# SH3_-_BATTERY_MANAGER.net
KiCad netlist of a schematic drawn in Altium Designer
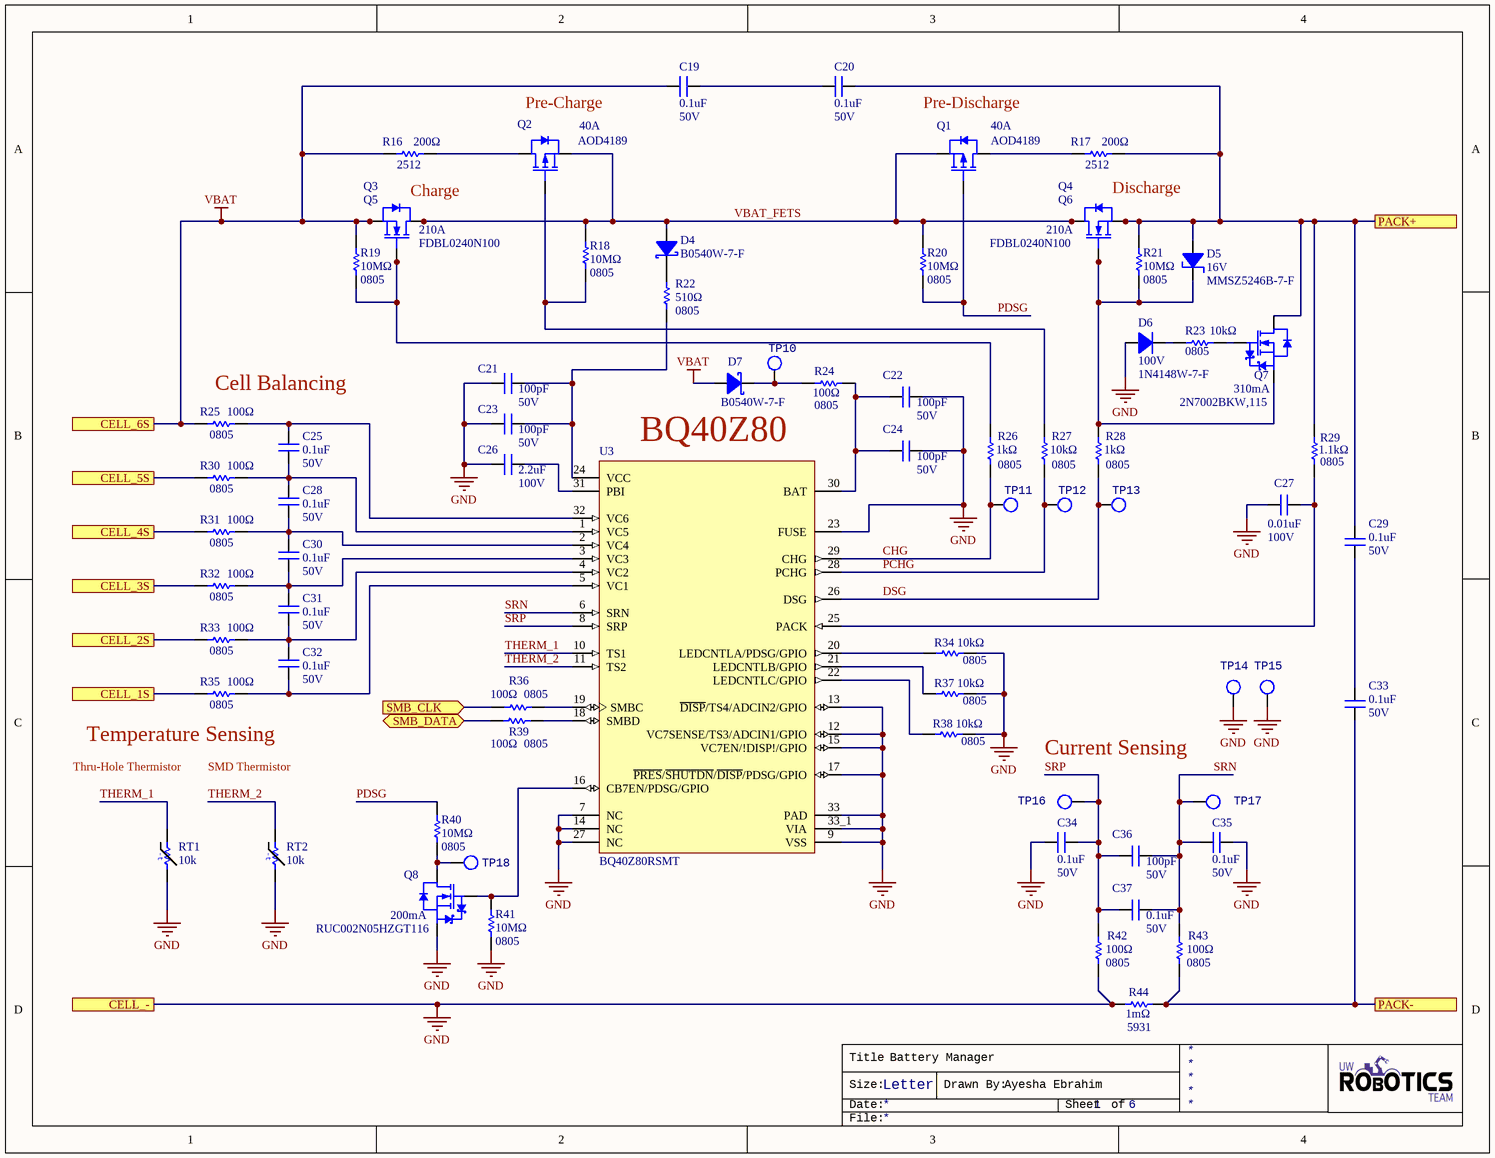
[diagram p0: SH3 - BATTERY MANAGER.SchDoc]

(export (version "E")
  (design (tool "Eeschema 10.0.6"))
  (components
    (comp (ref "C19")
      (value "0.1uF")
      (footprint "CAPC2012X140N")
      (description "CAP CER 0.1UF 50V X7R 0805")
      (fields
        (field (name "TOLERANCE") "10%")
        (field (name "VOLTAGE RATING") "50V")
        (field (name "Comment") "CAP_0.1uF_50V_0805")
      )
      (libsource (lib "UWRT_Schematic_Library_2020") (part "CAP_0.1uF_50V_0805"))
    )
    (comp (ref "C20")
      (value "0.1uF")
      (footprint "CAPC2012X140N")
      (description "CAP CER 0.1UF 50V X7R 0805")
      (fields
        (field (name "TOLERANCE") "10%")
        (field (name "VOLTAGE RATING") "50V")
        (field (name "Comment") "CAP_0.1uF_50V_0805")
      )
      (libsource (lib "UWRT_Schematic_Library_2020") (part "CAP_0.1uF_50V_0805"))
    )
    (comp (ref "C21")
      (value "100pF")
      (footprint "CAPC2012X140N")
      (description "CAP CER 100PF 50V C0G/NP0 0805")
      (fields
        (field (name "TOLERANCE") "5%")
        (field (name "VOLTAGE RATING") "50V")
        (field (name "Comment") "CAP_100pF_50V_0805")
      )
      (libsource (lib "UWRT_Schematic_Library_2020") (part "CAP_100pF_50V_0805"))
    )
    (comp (ref "C22")
      (value "100pF")
      (footprint "CAPC2012X140N")
      (description "CAP CER 100PF 50V C0G/NP0 0805")
      (fields
        (field (name "TOLERANCE") "5%")
        (field (name "VOLTAGE RATING") "50V")
        (field (name "Comment") "CAP_100pF_50V_0805")
      )
      (libsource (lib "UWRT_Schematic_Library_2020") (part "CAP_100pF_50V_0805"))
    )
    (comp (ref "C23")
      (value "100pF")
      (footprint "CAPC2012X140N")
      (description "CAP CER 100PF 50V C0G/NP0 0805")
      (fields
        (field (name "TOLERANCE") "5%")
        (field (name "VOLTAGE RATING") "50V")
        (field (name "Comment") "CAP_100pF_50V_0805")
      )
      (libsource (lib "UWRT_Schematic_Library_2020") (part "CAP_100pF_50V_0805"))
    )
    (comp (ref "C24")
      (value "100pF")
      (footprint "CAPC2012X140N")
      (description "CAP CER 100PF 50V C0G/NP0 0805")
      (fields
        (field (name "TOLERANCE") "5%")
        (field (name "VOLTAGE RATING") "50V")
        (field (name "Comment") "CAP_100pF_50V_0805")
      )
      (libsource (lib "UWRT_Schematic_Library_2020") (part "CAP_100pF_50V_0805"))
    )
    (comp (ref "C25")
      (value "0.1uF")
      (footprint "CAPC2012X140N")
      (description "CAP CER 0.1UF 50V X7R 0805")
      (fields
        (field (name "TOLERANCE") "10%")
        (field (name "VOLTAGE RATING") "50V")
        (field (name "Comment") "CAP_0.1uF_50V_0805")
      )
      (libsource (lib "UWRT_Schematic_Library_2020") (part "CAP_0.1uF_50V_0805"))
    )
    (comp (ref "C26")
      (value "2.2uF")
      (footprint "CAPC1210(3225)")
      (description "CAP CER 2.2UF 100V X7R 1210")
      (fields
        (field (name "TOLERANCE") "10%")
        (field (name "VOLTAGE RATING") "100V")
        (field (name "Comment") "CAP_2.2uF_100V_1210")
      )
      (libsource (lib "UWRT_Schematic_Library_2020") (part "CAP_2.2uF_100V_1210"))
    )
    (comp (ref "C27")
      (value "0.01uF")
      (footprint "CAPC2012X140N")
      (description "CAP CER 10000PF 100V X7R 0805")
      (fields
        (field (name "TOLERANCE") "10%")
        (field (name "VOLTAGE RATING") "100V")
        (field (name "Comment") "CAP_0.01uF_100V_0805")
      )
      (libsource (lib "UWRT_Schematic_Library_2020") (part "CAP_0.01uF_100V_0805"))
    )
    (comp (ref "C28")
      (value "0.1uF")
      (footprint "CAPC2012X140N")
      (description "CAP CER 0.1UF 50V X7R 0805")
      (fields
        (field (name "TOLERANCE") "10%")
        (field (name "VOLTAGE RATING") "50V")
        (field (name "Comment") "CAP_0.1uF_50V_0805")
      )
      (libsource (lib "UWRT_Schematic_Library_2020") (part "CAP_0.1uF_50V_0805"))
    )
    (comp (ref "C29")
      (value "0.1uF")
      (footprint "CAPC2012X140N")
      (description "CAP CER 0.1UF 50V X7R 0805")
      (fields
        (field (name "TOLERANCE") "10%")
        (field (name "VOLTAGE RATING") "50V")
        (field (name "Comment") "CAP_0.1uF_50V_0805")
      )
      (libsource (lib "UWRT_Schematic_Library_2020") (part "CAP_0.1uF_50V_0805"))
    )
    (comp (ref "C30")
      (value "0.1uF")
      (footprint "CAPC2012X140N")
      (description "CAP CER 0.1UF 50V X7R 0805")
      (fields
        (field (name "TOLERANCE") "10%")
        (field (name "VOLTAGE RATING") "50V")
        (field (name "Comment") "CAP_0.1uF_50V_0805")
      )
      (libsource (lib "UWRT_Schematic_Library_2020") (part "CAP_0.1uF_50V_0805"))
    )
    (comp (ref "C31")
      (value "0.1uF")
      (footprint "CAPC2012X140N")
      (description "CAP CER 0.1UF 50V X7R 0805")
      (fields
        (field (name "TOLERANCE") "10%")
        (field (name "VOLTAGE RATING") "50V")
        (field (name "Comment") "CAP_0.1uF_50V_0805")
      )
      (libsource (lib "UWRT_Schematic_Library_2020") (part "CAP_0.1uF_50V_0805"))
    )
    (comp (ref "C32")
      (value "0.1uF")
      (footprint "CAPC2012X140N")
      (description "CAP CER 0.1UF 50V X7R 0805")
      (fields
        (field (name "TOLERANCE") "10%")
        (field (name "VOLTAGE RATING") "50V")
        (field (name "Comment") "CAP_0.1uF_50V_0805")
      )
      (libsource (lib "UWRT_Schematic_Library_2020") (part "CAP_0.1uF_50V_0805"))
    )
    (comp (ref "C33")
      (value "0.1uF")
      (footprint "CAPC2012X140N")
      (description "CAP CER 0.1UF 50V X7R 0805")
      (fields
        (field (name "TOLERANCE") "10%")
        (field (name "VOLTAGE RATING") "50V")
        (field (name "Comment") "CAP_0.1uF_50V_0805")
      )
      (libsource (lib "UWRT_Schematic_Library_2020") (part "CAP_0.1uF_50V_0805"))
    )
    (comp (ref "C34")
      (value "0.1uF")
      (footprint "CAPC2012X140N")
      (description "CAP CER 0.1UF 50V X7R 0805")
      (fields
        (field (name "TOLERANCE") "10%")
        (field (name "VOLTAGE RATING") "50V")
        (field (name "Comment") "CAP_0.1uF_50V_0805")
      )
      (libsource (lib "UWRT_Schematic_Library_2020") (part "CAP_0.1uF_50V_0805"))
    )
    (comp (ref "C35")
      (value "0.1uF")
      (footprint "CAPC2012X140N")
      (description "CAP CER 0.1UF 50V X7R 0805")
      (fields
        (field (name "TOLERANCE") "10%")
        (field (name "VOLTAGE RATING") "50V")
        (field (name "Comment") "CAP_0.1uF_50V_0805")
      )
      (libsource (lib "UWRT_Schematic_Library_2020") (part "CAP_0.1uF_50V_0805"))
    )
    (comp (ref "C36")
      (value "100pF")
      (footprint "CAPC2012X140N")
      (description "CAP CER 100PF 50V C0G/NP0 0805")
      (fields
        (field (name "TOLERANCE") "5%")
        (field (name "VOLTAGE RATING") "50V")
        (field (name "Comment") "CAP_100pF_50V_0805")
      )
      (libsource (lib "UWRT_Schematic_Library_2020") (part "CAP_100pF_50V_0805"))
    )
    (comp (ref "C37")
      (value "0.1uF")
      (footprint "CAPC2012X140N")
      (description "CAP CER 0.1UF 50V X7R 0805")
      (fields
        (field (name "TOLERANCE") "10%")
        (field (name "VOLTAGE RATING") "50V")
        (field (name "Comment") "CAP_0.1uF_50V_0805")
      )
      (libsource (lib "UWRT_Schematic_Library_2020") (part "CAP_0.1uF_50V_0805"))
    )
    (comp (ref "D4")
      (value "B0540W-7-F")
      (footprint "SOD-123_FLAT")
      (description "DIODE SCHOTTKY 40V 500MA SOD123")
      (fields
        (field (name "MANUFACTURER") "Diodes Inc.")
        (field (name "OCTOPART") "https://octopart.com/b0540w-7-f-diodes+inc.-325656")
        (field (name "MANUFACTURER PART NUMBER 1") "B0540W-7-F")
      )
      (libsource (lib "UWRT_Schematic_Library_2020") (part "DIO_SCHOTTKY_40V_500mA"))
    )
    (comp (ref "D5")
      (value "DIO_ZENER_16V")
      (footprint "SOD-123_FLAT")
      (description "DIODE ZENER 16V 500MW SOD123")
      (fields
        (field (name "MANUFACTURER PART NUMBER 1") "MMSZ5246B-7-F")
        (field (name "ZENER VOLTAGE") "16V")
        (field (name "TOLERANCE") "5%")
      )
      (libsource (lib "UWRT_Schematic_Library_2020") (part "DIO_ZENER_16V"))
    )
    (comp (ref "D6")
      (value "100V")
      (footprint "SOD-123_FLAT")
      (description "DIODE GEN PURP 100V 300MA SOD123")
      (fields
        (field (name "MANUFACTURER PART NUMBER 1") "1N4148W-7-F")
        (field (name "Comment") "1N4148W-7-F")
      )
      (libsource (lib "UWRT_Schematic_Library_2020") (part "DIO_100V_300mA"))
    )
    (comp (ref "D7")
      (value "B0540W-7-F")
      (footprint "SOD-123_FLAT")
      (description "DIODE SCHOTTKY 40V 500MA SOD123")
      (fields
        (field (name "MANUFACTURER") "Diodes Inc.")
        (field (name "MANUFACTURER PART NUMBER") "B0540W-7-F")
        (field (name "OCTOPART") "https://octopart.com/b0540w-7-f-diodes+inc.-325656")
      )
      (libsource (lib "UWRT_Schematic_Library_2020") (part "DIO_SCHOTTKY_40V_500mA"))
    )
    (comp (ref "Q1")
      (value "PMOS_40V_40A")
      (footprint "D-PAK")
      (description "MOSFET P-CH 40V 40A TO252")
      (fields (field (name "MANUFACTURER PART NUMBER 1") "AOD4189") (field (name "ID") "40A"))
      (libsource (lib "UWRT_Schematic_Library_2020") (part "PMOS_40V_40A"))
    )
    (comp (ref "Q2")
      (value "PMOS_40V_40A")
      (footprint "D-PAK")
      (description "MOSFET P-CH 40V 40A TO252")
      (fields (field (name "MANUFACTURER PART NUMBER 1") "AOD4189") (field (name "ID") "40A"))
      (libsource (lib "UWRT_Schematic_Library_2020") (part "PMOS_40V_40A"))
    )
    (comp (ref "Q3")
      (value "NMOS_100V_210A")
      (footprint "8-HPSOF")
      (description "MOSFET N-CH 100V 210A POWER56")
      (fields (field (name "MANUFACTURER PART NUMBER 1") "FDBL0240N100") (field (name "ID") "210A"))
      (libsource (lib "UWRT_Schematic_Library_2020") (part "NMOS_100V_210A"))
    )
    (comp (ref "Q4")
      (value "NMOS_100V_210A")
      (footprint "8-HPSOF")
      (description "MOSFET N-CH 100V 210A POWER56")
      (fields (field (name "MANUFACTURER PART NUMBER 1") "FDBL0240N100") (field (name "ID") "210A"))
      (libsource (lib "UWRT_Schematic_Library_2020") (part "NMOS_100V_210A"))
    )
    (comp (ref "Q5")
      (value "NMOS_100V_210A")
      (footprint "8-HPSOF")
      (description "MOSFET N-CH 100V 210A POWER56")
      (libsource (lib "UWRT_Schematic_Library_2020") (part "NMOS_100V_210A"))
    )
    (comp (ref "Q6")
      (value "NMOS_100V_210A")
      (footprint "8-HPSOF")
      (description "MOSFET N-CH 100V 210A POWER56")
      (libsource (lib "UWRT_Schematic_Library_2020") (part "NMOS_100V_210A"))
    )
    (comp (ref "Q7")
      (value "NMOS_60V_310mA")
      (footprint "SOT323")
      (description "NMOS N-CH 60V 310mA SOT-323")
      (fields (field (name "MANUFACTURER PART NUMBER 1") "2N7002BKW,115") (field (name "ID") "310mA"))
      (libsource (lib "UWRT_Schematic_Library_2020") (part "NMOS_60V_310mA"))
    )
    (comp (ref "Q8")
      (value "NMOS_50V_200mA")
      (footprint "SOT23-3")
      (description "NMOS N-CH 50V 200mA 1.2V DRIVE SOT-23-3")
      (fields (field (name "MANUFACTURER PART NUMBER 1") "RUC002N05HZGT116") (field (name "ID") "200mA"))
      (libsource (lib "UWRT_Schematic_Library_2020") (part "NMOS_50V_200mA"))
    )
    (comp (ref "R16")
      (value "200Ω")
      (footprint "RESC6532X75N")
      (description "RES 200 OHM 5% 1W 2512")
      (fields
        (field (name "PACKAGE") "2512")
        (field (name "TOLERANCE") "5%")
        (field (name "Comment") "RES_200Ω_2512")
      )
      (libsource (lib "UWRT_Schematic_Library_2020") (part "RES_200Ω_2512"))
    )
    (comp (ref "R17")
      (value "200Ω")
      (footprint "RESC6532X75N")
      (description "RES 200 OHM 5% 1W 2512")
      (fields
        (field (name "PACKAGE") "2512")
        (field (name "TOLERANCE") "5%")
        (field (name "Comment") "RES_200Ω_2512")
      )
      (libsource (lib "UWRT_Schematic_Library_2020") (part "RES_200Ω_2512"))
    )
    (comp (ref "R18")
      (value "10MΩ")
      (footprint "RESC2012X60N")
      (description "RES SMD 10M OHM 5% 1/8W 0805")
      (fields
        (field (name "TOLERANCE") "5%")
        (field (name "CASE CODE (IMPERIAL)") "0805")
        (field (name "Comment") "RES_10MΩ_0805")
      )
      (libsource (lib "UWRT_Schematic_Library_2020") (part "RES_10MΩ_0805"))
    )
    (comp (ref "R19")
      (value "10MΩ")
      (footprint "RESC2012X60N")
      (description "RES SMD 10M OHM 5% 1/8W 0805")
      (fields
        (field (name "TOLERANCE") "5%")
        (field (name "CASE CODE (IMPERIAL)") "0805")
        (field (name "Comment") "RES_10MΩ_0805")
      )
      (libsource (lib "UWRT_Schematic_Library_2020") (part "RES_10MΩ_0805"))
    )
    (comp (ref "R20")
      (value "10MΩ")
      (footprint "RESC2012X60N")
      (description "RES SMD 10M OHM 5% 1/8W 0805")
      (fields
        (field (name "TOLERANCE") "5%")
        (field (name "CASE CODE (IMPERIAL)") "0805")
        (field (name "Comment") "RES_10MΩ_0805")
      )
      (libsource (lib "UWRT_Schematic_Library_2020") (part "RES_10MΩ_0805"))
    )
    (comp (ref "R21")
      (value "10MΩ")
      (footprint "RESC2012X60N")
      (description "RES SMD 10M OHM 5% 1/8W 0805")
      (fields
        (field (name "TOLERANCE") "5%")
        (field (name "CASE CODE (IMPERIAL)") "0805")
        (field (name "Comment") "RES_10MΩ_0805")
      )
      (libsource (lib "UWRT_Schematic_Library_2020") (part "RES_10MΩ_0805"))
    )
    (comp (ref "R22")
      (value "510Ω")
      (footprint "RESC2012X60N")
      (description "RES SMD 510 OHM 1% 1/8W 0805")
      (fields
        (field (name "CASE CODE (IMPERIAL)") "0805")
        (field (name "TOLERANCE") "1%")
        (field (name "Comment") "RES_510Ω_0805")
      )
      (libsource (lib "UWRT_Schematic_Library_2020") (part "RES_510Ω_0805"))
    )
    (comp (ref "R23")
      (value "10kΩ")
      (footprint "RESC2012X60N")
      (description "RES SMD 10K OHM 1% 1/8W 0805")
      (fields
        (field (name "CASE CODE (IMPERIAL)") "0805")
        (field (name "TOLERANCE") "1%")
        (field (name "Comment") "RES_10kΩ_0805")
      )
      (libsource (lib "UWRT_Schematic_Library_2020") (part "RES_10kΩ_0805"))
    )
    (comp (ref "R24")
      (value "100Ω")
      (footprint "RESC2012X60N")
      (description "RES SMD 100 OHM 1% 1/8W 0805")
      (fields (field (name "CASE CODE (IMPERIAL)") "0805") (field (name "Comment") "RES_100Ω_0805"))
      (libsource (lib "UWRT_Schematic_Library_2020") (part "RES_100Ω_0805"))
    )
    (comp (ref "R25")
      (value "100Ω")
      (footprint "RESC2012X60N")
      (description "RES SMD 100 OHM 1% 1/8W 0805")
      (fields (field (name "CASE CODE (IMPERIAL)") "0805") (field (name "Comment") "RES_100Ω_0805"))
      (libsource (lib "UWRT_Schematic_Library_2020") (part "RES_100Ω_0805"))
    )
    (comp (ref "R26")
      (value "1kΩ")
      (footprint "RESC2012X60N")
      (description "RES SMD 1K OHM 1% 1/8W 0805")
      (fields
        (field (name "CASE CODE (IMPERIAL)") "0805")
        (field (name "TOLERANCE") "1%")
        (field (name "Comment") "RES_1kΩ_0805")
      )
      (libsource (lib "UWRT_Schematic_Library_2020") (part "RES_1kΩ_0805"))
    )
    (comp (ref "R27")
      (value "10kΩ")
      (footprint "RESC2012X60N")
      (description "RES SMD 10K OHM 1% 1/8W 0805")
      (fields
        (field (name "CASE CODE (IMPERIAL)") "0805")
        (field (name "TOLERANCE") "1%")
        (field (name "Comment") "RES_10kΩ_0805")
      )
      (libsource (lib "UWRT_Schematic_Library_2020") (part "RES_10kΩ_0805"))
    )
    (comp (ref "R28")
      (value "1kΩ")
      (footprint "RESC2012X60N")
      (description "RES SMD 1K OHM 1% 1/8W 0805")
      (fields
        (field (name "CASE CODE (IMPERIAL)") "0805")
        (field (name "TOLERANCE") "1%")
        (field (name "Comment") "RES_1kΩ_0805")
      )
      (libsource (lib "UWRT_Schematic_Library_2020") (part "RES_1kΩ_0805"))
    )
    (comp (ref "R29")
      (value "1.1kΩ")
      (footprint "RESC2012X60N")
      (description "RES SMD 1.1K OHM 1% 1/8W 0805")
      (fields
        (field (name "CASE CODE (IMPERIAL)") "0805")
        (field (name "TOLERANCE") "1%")
        (field (name "Comment") "RES_1.1kΩ_0805")
      )
      (libsource (lib "UWRT_Schematic_Library_2020") (part "RES_1.1kΩ_0805"))
    )
    (comp (ref "R30")
      (value "100Ω")
      (footprint "RESC2012X60N")
      (description "RES SMD 100 OHM 1% 1/8W 0805")
      (fields (field (name "CASE CODE (IMPERIAL)") "0805") (field (name "Comment") "RES_100Ω_0805"))
      (libsource (lib "UWRT_Schematic_Library_2020") (part "RES_100Ω_0805"))
    )
    (comp (ref "R31")
      (value "100Ω")
      (footprint "RESC2012X60N")
      (description "RES SMD 100 OHM 1% 1/8W 0805")
      (fields (field (name "CASE CODE (IMPERIAL)") "0805") (field (name "Comment") "RES_100Ω_0805"))
      (libsource (lib "UWRT_Schematic_Library_2020") (part "RES_100Ω_0805"))
    )
    (comp (ref "R32")
      (value "100Ω")
      (footprint "RESC2012X60N")
      (description "RES SMD 100 OHM 1% 1/8W 0805")
      (fields (field (name "CASE CODE (IMPERIAL)") "0805") (field (name "Comment") "RES_100Ω_0805"))
      (libsource (lib "UWRT_Schematic_Library_2020") (part "RES_100Ω_0805"))
    )
    (comp (ref "R33")
      (value "100Ω")
      (footprint "RESC2012X60N")
      (description "RES SMD 100 OHM 1% 1/8W 0805")
      (fields (field (name "CASE CODE (IMPERIAL)") "0805") (field (name "Comment") "RES_100Ω_0805"))
      (libsource (lib "UWRT_Schematic_Library_2020") (part "RES_100Ω_0805"))
    )
    (comp (ref "R34")
      (value "10kΩ")
      (footprint "RESC2012X60N")
      (description "RES SMD 10K OHM 1% 1/8W 0805")
      (fields
        (field (name "CASE CODE (IMPERIAL)") "0805")
        (field (name "TOLERANCE") "1%")
        (field (name "Comment") "RES_10kΩ_0805")
      )
      (libsource (lib "UWRT_Schematic_Library_2020") (part "RES_10kΩ_0805"))
    )
    (comp (ref "R35")
      (value "100Ω")
      (footprint "RESC2012X60N")
      (description "RES SMD 100 OHM 1% 1/8W 0805")
      (fields (field (name "CASE CODE (IMPERIAL)") "0805") (field (name "Comment") "RES_100Ω_0805"))
      (libsource (lib "UWRT_Schematic_Library_2020") (part "RES_100Ω_0805"))
    )
    (comp (ref "R36")
      (value "100Ω")
      (footprint "RESC2012X60N")
      (description "RES SMD 100 OHM 1% 1/8W 0805")
      (fields (field (name "CASE CODE (IMPERIAL)") "0805") (field (name "Comment") "RES_100Ω_0805"))
      (libsource (lib "UWRT_Schematic_Library_2020") (part "RES_100Ω_0805"))
    )
    (comp (ref "R37")
      (value "10kΩ")
      (footprint "RESC2012X60N")
      (description "RES SMD 10K OHM 1% 1/8W 0805")
      (fields
        (field (name "CASE CODE (IMPERIAL)") "0805")
        (field (name "TOLERANCE") "1%")
        (field (name "Comment") "RES_10kΩ_0805")
      )
      (libsource (lib "UWRT_Schematic_Library_2020") (part "RES_10kΩ_0805"))
    )
    (comp (ref "R38")
      (value "10kΩ")
      (footprint "RESC2012X60N")
      (description "RES SMD 10K OHM 1% 1/8W 0805")
      (fields
        (field (name "CASE CODE (IMPERIAL)") "0805")
        (field (name "TOLERANCE") "1%")
        (field (name "Comment") "RES_10kΩ_0805")
      )
      (libsource (lib "UWRT_Schematic_Library_2020") (part "RES_10kΩ_0805"))
    )
    (comp (ref "R39")
      (value "100Ω")
      (footprint "RESC2012X60N")
      (description "RES SMD 100 OHM 1% 1/8W 0805")
      (fields (field (name "CASE CODE (IMPERIAL)") "0805") (field (name "Comment") "RES_100Ω_0805"))
      (libsource (lib "UWRT_Schematic_Library_2020") (part "RES_100Ω_0805"))
    )
    (comp (ref "R40")
      (value "10MΩ")
      (footprint "RESC2012X60N")
      (description "RES SMD 10M OHM 5% 1/8W 0805")
      (fields
        (field (name "TOLERANCE") "5%")
        (field (name "CASE CODE (IMPERIAL)") "0805")
        (field (name "Comment") "RES_10MΩ_0805")
      )
      (libsource (lib "UWRT_Schematic_Library_2020") (part "RES_10MΩ_0805"))
    )
    (comp (ref "R41")
      (value "10MΩ")
      (footprint "RESC2012X60N")
      (description "RES SMD 10M OHM 5% 1/8W 0805")
      (fields
        (field (name "TOLERANCE") "5%")
        (field (name "CASE CODE (IMPERIAL)") "0805")
        (field (name "Comment") "RES_10MΩ_0805")
      )
      (libsource (lib "UWRT_Schematic_Library_2020") (part "RES_10MΩ_0805"))
    )
    (comp (ref "R42")
      (value "100Ω")
      (footprint "RESC2012X60N")
      (description "RES SMD 100 OHM 1% 1/8W 0805")
      (fields (field (name "CASE CODE (IMPERIAL)") "0805") (field (name "Comment") "RES_100Ω_0805"))
      (libsource (lib "UWRT_Schematic_Library_2020") (part "RES_100Ω_0805"))
    )
    (comp (ref "R43")
      (value "100Ω")
      (footprint "RESC2012X60N")
      (description "RES SMD 100 OHM 1% 1/8W 0805")
      (fields (field (name "CASE CODE (IMPERIAL)") "0805") (field (name "Comment") "RES_100Ω_0805"))
      (libsource (lib "UWRT_Schematic_Library_2020") (part "RES_100Ω_0805"))
    )
    (comp (ref "R44")
      (value "1mΩ")
      (footprint "RES-5931")
      (description "RES 0.001 OHM 1% 10W 5931")
      (fields
        (field (name "PACKAGE") "5931")
        (field (name "TOLERANCE") "1%")
        (field (name "Comment") "RES_1mΩ_5931")
      )
      (libsource (lib "UWRT_Schematic_Library_2020") (part "RES_1mΩ_5931"))
    )
    (comp (ref "RT1")
      (value "THERM_10k_FREE_HANGING")
      (footprint "HDR1X2 - PTH Thermistor")
      (description "THERMISTOR NTC 10KOHM 3380K BEAD")
      (fields (field (name "TOLERANCE") "1%") (field (name "RESISTANCE") "10k"))
      (libsource (lib "UWRT_Schematic_Library_2020") (part "THERM_10k_FREE_HANGING"))
    )
    (comp (ref "RT2")
      (value "THERM_10k_0603")
      (footprint "RESC0603(1608)_N")
      (description "THERMISTOR NTC 10K 1% OHM 0603")
      (fields (field (name "TOLERANCE") "1%") (field (name "RESISTANCE") "10k"))
      (libsource (lib "UWRT_Schematic_Library_2020") (part "THERM_10k_0603"))
    )
    (comp (ref "TP10")
      (value "TESTPOINT_LOOP")
      (footprint "TESTPOINT_LOOP")
      (description "Loop testpoint through-hole pad")
      (libsource (lib "UWRT_Schematic_Library_2020") (part "TESTPOINT_LOOP"))
    )
    (comp (ref "TP11")
      (value "TESTPOINT_LOOP")
      (footprint "TESTPOINT_LOOP")
      (description "Loop testpoint through-hole pad")
      (libsource (lib "UWRT_Schematic_Library_2020") (part "TESTPOINT_LOOP"))
    )
    (comp (ref "TP12")
      (value "TESTPOINT_LOOP")
      (footprint "TESTPOINT_LOOP")
      (description "Loop testpoint through-hole pad")
      (libsource (lib "UWRT_Schematic_Library_2020") (part "TESTPOINT_LOOP"))
    )
    (comp (ref "TP13")
      (value "TESTPOINT_LOOP")
      (footprint "TESTPOINT_LOOP")
      (description "Loop testpoint through-hole pad")
      (libsource (lib "UWRT_Schematic_Library_2020") (part "TESTPOINT_LOOP"))
    )
    (comp (ref "TP14")
      (value "TESTPOINT_LOOP")
      (footprint "TESTPOINT_LOOP")
      (description "Loop testpoint through-hole pad")
      (libsource (lib "UWRT_Schematic_Library_2020") (part "TESTPOINT_LOOP"))
    )
    (comp (ref "TP15")
      (value "TESTPOINT_LOOP")
      (footprint "TESTPOINT_LOOP")
      (description "Loop testpoint through-hole pad")
      (libsource (lib "UWRT_Schematic_Library_2020") (part "TESTPOINT_LOOP"))
    )
    (comp (ref "TP16")
      (value "TESTPOINT_LOOP")
      (footprint "TESTPOINT_LOOP")
      (description "Loop testpoint through-hole pad")
      (libsource (lib "UWRT_Schematic_Library_2020") (part "TESTPOINT_LOOP"))
    )
    (comp (ref "TP17")
      (value "TESTPOINT_LOOP")
      (footprint "TESTPOINT_LOOP")
      (description "Loop testpoint through-hole pad")
      (libsource (lib "UWRT_Schematic_Library_2020") (part "TESTPOINT_LOOP"))
    )
    (comp (ref "TP18")
      (value "TESTPOINT_LOOP")
      (footprint "TESTPOINT_LOOP")
      (description "Loop testpoint through-hole pad")
      (libsource (lib "UWRT_Schematic_Library_2020") (part "TESTPOINT_LOOP"))
    )
    (comp (ref "U3")
      (value "BQ40Z80RSMT")
      (footprint "BQ40Z80RSMT")
      (description "POWER MANAGEMENT IC: Battery Multi-Function Controller IC Lithium Ion/Polymer 32-VQFN (4x4)")
      (libsource (lib "UWRT_Schematic_Library_2020") (part "BATT_MANAGER"))
    )
  )
  (nets
    (net (code "1") (name "/CELL_1S") (class "Default")
      (node (ref "R35") (pin "1") (pinfunction "1_1") (pintype "passive"))
    )
    (net (code "2") (name "/CELL_2S") (class "Default")
      (node (ref "R33") (pin "1") (pinfunction "1_1") (pintype "passive"))
    )
    (net (code "3") (name "/CELL_3S") (class "Default")
      (node (ref "R32") (pin "1") (pinfunction "1_1") (pintype "passive"))
    )
    (net (code "4") (name "/CELL_4S") (class "Default")
      (node (ref "R31") (pin "1") (pinfunction "1_1") (pintype "passive"))
    )
    (net (code "5") (name "/CELL_5S") (class "Default")
      (node (ref "R30") (pin "1") (pinfunction "1_1") (pintype "passive"))
    )
    (net (code "6") (name "/CHG") (class "Default")
      (node (ref "R26") (pin "1") (pinfunction "1_1") (pintype "passive"))
      (node (ref "TP11") (pin "1") (pintype "passive"))
      (node (ref "U3") (pin "29") (pinfunction "CHG_29") (pintype "output"))
    )
    (net (code "7") (name "/DSG") (class "Default")
      (node (ref "R28") (pin "1") (pinfunction "1_1") (pintype "passive"))
      (node (ref "TP13") (pin "1") (pintype "passive"))
      (node (ref "U3") (pin "26") (pinfunction "DSG_26") (pintype "output"))
    )
    (net (code "8") (name "/PACK+") (class "Default")
      (node (ref "C20") (pin "2") (pinfunction "2_2") (pintype "passive"))
      (node (ref "C29") (pin "2") (pinfunction "2_2") (pintype "passive"))
      (node (ref "D5") (pin "1") (pinfunction "Anode_1") (pintype "passive"))
      (node (ref "Q4") (pin "2") (pinfunction "Source_2") (pintype "passive"))
      (node (ref "Q6") (pin "2") (pinfunction "Source_2") (pintype "passive"))
      (node (ref "Q7") (pin "3") (pinfunction "D_3") (pintype "passive"))
      (node (ref "R17") (pin "2") (pinfunction "2_2") (pintype "passive"))
      (node (ref "R21") (pin "2") (pinfunction "2_2") (pintype "passive"))
      (node (ref "R29") (pin "2") (pinfunction "2_2") (pintype "passive"))
    )
    (net (code "9") (name "/PACK-") (class "Default")
      (node (ref "C33") (pin "1") (pinfunction "1_1") (pintype "passive"))
      (node (ref "R43") (pin "1") (pinfunction "1_1") (pintype "passive"))
      (node (ref "R44") (pin "2") (pinfunction "2_2") (pintype "passive"))
    )
    (net (code "10") (name "/PCHG") (class "Default")
      (node (ref "R27") (pin "1") (pinfunction "1_1") (pintype "passive"))
      (node (ref "TP12") (pin "1") (pintype "passive"))
      (node (ref "U3") (pin "28") (pinfunction "PCHG_28") (pintype "output"))
    )
    (net (code "11") (name "/PDSG") (class "Default")
      (node (ref "Q1") (pin "2") (pinfunction "Gate_2") (pintype "passive"))
      (node (ref "R20") (pin "1") (pinfunction "1_1") (pintype "passive"))
      (node (ref "R40") (pin "2") (pinfunction "2_2") (pintype "passive"))
    )
    (net (code "12") (name "/SMB_CLK") (class "Default")
      (node (ref "R36") (pin "1") (pinfunction "1_1") (pintype "passive"))
    )
    (net (code "13") (name "/SMB_DATA") (class "Default")
      (node (ref "R39") (pin "1") (pinfunction "1_1") (pintype "passive"))
    )
    (net (code "14") (name "/SRN") (class "Default")
      (node (ref "C35") (pin "1") (pinfunction "1_1") (pintype "passive"))
      (node (ref "C36") (pin "2") (pinfunction "2_2") (pintype "passive"))
      (node (ref "C37") (pin "2") (pinfunction "2_2") (pintype "passive"))
      (node (ref "R43") (pin "2") (pinfunction "2_2") (pintype "passive"))
      (node (ref "TP17") (pin "1") (pintype "passive"))
      (node (ref "U3") (pin "6") (pinfunction "SRN_6") (pintype "input"))
    )
    (net (code "15") (name "/SRP") (class "Default")
      (node (ref "C34") (pin "2") (pinfunction "2_2") (pintype "passive"))
      (node (ref "C36") (pin "1") (pinfunction "1_1") (pintype "passive"))
      (node (ref "C37") (pin "1") (pinfunction "1_1") (pintype "passive"))
      (node (ref "R42") (pin "2") (pinfunction "2_2") (pintype "passive"))
      (node (ref "TP16") (pin "1") (pintype "passive"))
      (node (ref "U3") (pin "8") (pinfunction "SRP_8") (pintype "input"))
    )
    (net (code "16") (name "/THERM_1") (class "Default")
      (node (ref "RT1") (pin "1") (pinfunction "1_1") (pintype "passive"))
      (node (ref "U3") (pin "10") (pinfunction "TS1_10") (pintype "input"))
    )
    (net (code "17") (name "/THERM_2") (class "Default")
      (node (ref "RT2") (pin "1") (pinfunction "1_1") (pintype "passive"))
      (node (ref "U3") (pin "11") (pinfunction "TS2_11") (pintype "input"))
    )
    (net (code "18") (name "/VBAT_FETS") (class "Default")
      (node (ref "D4") (pin "2") (pintype "passive"))
      (node (ref "Q1") (pin "3") (pinfunction "Source_3") (pintype "passive"))
      (node (ref "Q2") (pin "3") (pinfunction "Source_3") (pintype "passive"))
      (node (ref "Q3") (pin "3") (pinfunction "Drain_3") (pintype "passive"))
      (node (ref "Q4") (pin "3") (pinfunction "Drain_3") (pintype "passive"))
      (node (ref "Q5") (pin "3") (pinfunction "Drain_3") (pintype "passive"))
      (node (ref "Q6") (pin "3") (pinfunction "Drain_3") (pintype "passive"))
      (node (ref "R18") (pin "2") (pinfunction "2_2") (pintype "passive"))
      (node (ref "R20") (pin "2") (pinfunction "2_2") (pintype "passive"))
    )
    (net (code "19") (name "GND") (class "Default")
      (node (ref "C21") (pin "1") (pinfunction "1_1") (pintype "passive"))
      (node (ref "C22") (pin "2") (pinfunction "2_2") (pintype "passive"))
      (node (ref "C23") (pin "1") (pinfunction "1_1") (pintype "passive"))
      (node (ref "C24") (pin "2") (pinfunction "2_2") (pintype "passive"))
      (node (ref "C26") (pin "1") (pinfunction "1_1") (pintype "passive"))
      (node (ref "C27") (pin "1") (pinfunction "1_1") (pintype "passive"))
      (node (ref "C34") (pin "1") (pinfunction "1_1") (pintype "passive"))
      (node (ref "C35") (pin "2") (pinfunction "2_2") (pintype "passive"))
      (node (ref "D6") (pin "2") (pintype "passive"))
      (node (ref "Q8") (pin "2") (pinfunction "S_2") (pintype "passive"))
      (node (ref "R34") (pin "2") (pinfunction "2_2") (pintype "passive"))
      (node (ref "R37") (pin "2") (pinfunction "2_2") (pintype "passive"))
      (node (ref "R38") (pin "2") (pinfunction "2_2") (pintype "passive"))
      (node (ref "R41") (pin "1") (pinfunction "1_1") (pintype "passive"))
      (node (ref "R42") (pin "1") (pinfunction "1_1") (pintype "passive"))
      (node (ref "R44") (pin "1") (pinfunction "1_1") (pintype "passive"))
      (node (ref "RT1") (pin "2") (pinfunction "2_2") (pintype "passive"))
      (node (ref "RT2") (pin "2") (pinfunction "2_2") (pintype "passive"))
      (node (ref "TP14") (pin "1") (pintype "passive"))
      (node (ref "TP15") (pin "1") (pintype "passive"))
      (node (ref "U3") (pin "12") (pinfunction "VC7SENSE/TS3/ADCIN1/GPIO_12") (pintype "bidirectional"))
      (node (ref "U3") (pin "13") (pinfunction "~{DISP}/TS4/ADCIN2/GPIO_13") (pintype "bidirectional"))
      (node (ref "U3") (pin "14") (pinfunction "NC_14") (pintype "passive"))
      (node (ref "U3") (pin "15") (pinfunction "VC7EN/!DISP!/GPIO_15") (pintype "bidirectional"))
      (node (ref "U3") (pin "17") (pinfunction "~{PRES}/~{SHUTDN}/~{DISP}/PDSG/GPIO_17") (pintype "bidirectional"))
      (node (ref "U3") (pin "23") (pinfunction "FUSE_23") (pintype "passive"))
      (node (ref "U3") (pin "27") (pinfunction "NC_27") (pintype "passive"))
      (node (ref "U3") (pin "33") (pinfunction "PAD_33") (pintype "power_in"))
      (node (ref "U3") (pin "33_1") (pinfunction "VIA_33_1") (pintype "power_in"))
      (node (ref "U3") (pin "7") (pinfunction "NC_7") (pintype "passive"))
      (node (ref "U3") (pin "9") (pinfunction "VSS_9") (pintype "power_in"))
    )
    (net (code "20") (name "Net-(C19-Pad2)") (class "Default")
      (node (ref "C19") (pin "2") (pinfunction "2_2") (pintype "passive"))
      (node (ref "C20") (pin "1") (pinfunction "1_1") (pintype "passive"))
    )
    (net (code "21") (name "Net-(C29-Pad1)") (class "Default")
      (node (ref "C29") (pin "1") (pinfunction "1_1") (pintype "passive"))
      (node (ref "C33") (pin "2") (pinfunction "2_2") (pintype "passive"))
    )
    (net (code "22") (name "Net-(D4-Pad1)") (class "Default")
      (node (ref "D4") (pin "1") (pintype "passive"))
      (node (ref "R22") (pin "2") (pinfunction "2_2") (pintype "passive"))
    )
    (net (code "23") (name "Net-(D5-Cathode)") (class "Default")
      (node (ref "D5") (pin "2") (pinfunction "Cathode_2") (pintype "passive"))
      (node (ref "Q4") (pin "1") (pinfunction "Gate_1") (pintype "passive"))
      (node (ref "Q6") (pin "1") (pinfunction "Gate_1") (pintype "passive"))
      (node (ref "Q7") (pin "2") (pinfunction "S_2") (pintype "passive"))
      (node (ref "R21") (pin "1") (pinfunction "1_1") (pintype "passive"))
      (node (ref "R28") (pin "2") (pinfunction "2_2") (pintype "passive"))
    )
    (net (code "24") (name "Net-(D6-Pad1)") (class "Default")
      (node (ref "D6") (pin "1") (pintype "passive"))
      (node (ref "R23") (pin "1") (pinfunction "1_1") (pintype "passive"))
    )
    (net (code "25") (name "Net-(D7-Pad1)") (class "Default")
      (node (ref "D7") (pin "1") (pintype "passive"))
      (node (ref "R24") (pin "1") (pinfunction "1_1") (pintype "passive"))
      (node (ref "TP10") (pin "1") (pintype "passive"))
    )
    (net (code "26") (name "Net-(Q1-Drain)") (class "Default")
      (node (ref "Q1") (pin "1") (pinfunction "Drain_1") (pintype "passive"))
      (node (ref "R17") (pin "1") (pinfunction "1_1") (pintype "passive"))
    )
    (net (code "27") (name "Net-(Q2-Drain)") (class "Default")
      (node (ref "Q2") (pin "1") (pinfunction "Drain_1") (pintype "passive"))
      (node (ref "R16") (pin "2") (pinfunction "2_2") (pintype "passive"))
    )
    (net (code "28") (name "Net-(Q2-Gate)") (class "Default")
      (node (ref "Q2") (pin "2") (pinfunction "Gate_2") (pintype "passive"))
      (node (ref "R18") (pin "1") (pinfunction "1_1") (pintype "passive"))
      (node (ref "R27") (pin "2") (pinfunction "2_2") (pintype "passive"))
    )
    (net (code "29") (name "Net-(Q3-Gate)") (class "Default")
      (node (ref "Q3") (pin "1") (pinfunction "Gate_1") (pintype "passive"))
      (node (ref "Q5") (pin "1") (pinfunction "Gate_1") (pintype "passive"))
      (node (ref "R19") (pin "1") (pinfunction "1_1") (pintype "passive"))
      (node (ref "R26") (pin "2") (pinfunction "2_2") (pintype "passive"))
    )
    (net (code "30") (name "Net-(Q7-G)") (class "Default")
      (node (ref "Q7") (pin "1") (pinfunction "G_1") (pintype "passive"))
      (node (ref "R23") (pin "2") (pinfunction "2_2") (pintype "passive"))
    )
    (net (code "31") (name "Net-(Q8-D)") (class "Default")
      (node (ref "Q8") (pin "3") (pinfunction "D_3") (pintype "passive"))
      (node (ref "R40") (pin "1") (pinfunction "1_1") (pintype "passive"))
      (node (ref "TP18") (pin "1") (pintype "passive"))
    )
    (net (code "32") (name "Net-(Q8-G)") (class "Default")
      (node (ref "Q8") (pin "1") (pinfunction "G_1") (pintype "passive"))
      (node (ref "R41") (pin "2") (pinfunction "2_2") (pintype "passive"))
      (node (ref "U3") (pin "16") (pinfunction "CB7EN/PDSG/GPIO_16") (pintype "bidirectional"))
    )
    (net (code "33") (name "Net-(U3-BAT)") (class "Default")
      (node (ref "C22") (pin "1") (pinfunction "1_1") (pintype "passive"))
      (node (ref "C24") (pin "1") (pinfunction "1_1") (pintype "passive"))
      (node (ref "R24") (pin "2") (pinfunction "2_2") (pintype "passive"))
      (node (ref "U3") (pin "30") (pinfunction "BAT_30") (pintype "power_in"))
    )
    (net (code "34") (name "Net-(U3-LEDCNTLA{slash}PDSG{slash}GPIO)") (class "Default")
      (node (ref "R34") (pin "1") (pinfunction "1_1") (pintype "passive"))
      (node (ref "U3") (pin "20") (pinfunction "LEDCNTLA/PDSG/GPIO_20") (pintype "output"))
    )
    (net (code "35") (name "Net-(U3-LEDCNTLB{slash}GPIO)") (class "Default")
      (node (ref "R37") (pin "1") (pinfunction "1_1") (pintype "passive"))
      (node (ref "U3") (pin "21") (pinfunction "LEDCNTLB/GPIO_21") (pintype "output"))
    )
    (net (code "36") (name "Net-(U3-LEDCNTLC{slash}GPIO)") (class "Default")
      (node (ref "R38") (pin "1") (pinfunction "1_1") (pintype "passive"))
      (node (ref "U3") (pin "22") (pinfunction "LEDCNTLC/GPIO_22") (pintype "output"))
    )
    (net (code "37") (name "Net-(U3-PACK)") (class "Default")
      (node (ref "C27") (pin "2") (pinfunction "2_2") (pintype "passive"))
      (node (ref "R29") (pin "1") (pinfunction "1_1") (pintype "passive"))
      (node (ref "U3") (pin "25") (pinfunction "PACK_25") (pintype "input"))
    )
    (net (code "38") (name "Net-(U3-PBI)") (class "Default")
      (node (ref "C26") (pin "2") (pinfunction "2_2") (pintype "passive"))
      (node (ref "U3") (pin "31") (pinfunction "PBI_31") (pintype "power_in"))
    )
    (net (code "39") (name "Net-(U3-SMBC)") (class "Default")
      (node (ref "R36") (pin "2") (pinfunction "2_2") (pintype "passive"))
      (node (ref "U3") (pin "19") (pinfunction "SMBC_19") (pintype "bidirectional"))
    )
    (net (code "40") (name "Net-(U3-SMBD)") (class "Default")
      (node (ref "R39") (pin "2") (pinfunction "2_2") (pintype "passive"))
      (node (ref "U3") (pin "18") (pinfunction "SMBD_18") (pintype "bidirectional"))
    )
    (net (code "41") (name "Net-(U3-VC1)") (class "Default")
      (node (ref "C32") (pin "1") (pinfunction "1_1") (pintype "passive"))
      (node (ref "R35") (pin "2") (pinfunction "2_2") (pintype "passive"))
      (node (ref "U3") (pin "5") (pinfunction "VC1_5") (pintype "input"))
    )
    (net (code "42") (name "Net-(U3-VC2)") (class "Default")
      (node (ref "C31") (pin "1") (pinfunction "1_1") (pintype "passive"))
      (node (ref "C32") (pin "2") (pinfunction "2_2") (pintype "passive"))
      (node (ref "R33") (pin "2") (pinfunction "2_2") (pintype "passive"))
      (node (ref "U3") (pin "4") (pinfunction "VC2_4") (pintype "input"))
    )
    (net (code "43") (name "Net-(U3-VC3)") (class "Default")
      (node (ref "C30") (pin "1") (pinfunction "1_1") (pintype "passive"))
      (node (ref "C31") (pin "2") (pinfunction "2_2") (pintype "passive"))
      (node (ref "R32") (pin "2") (pinfunction "2_2") (pintype "passive"))
      (node (ref "U3") (pin "3") (pinfunction "VC3_3") (pintype "input"))
    )
    (net (code "44") (name "Net-(U3-VC4)") (class "Default")
      (node (ref "C28") (pin "1") (pinfunction "1_1") (pintype "passive"))
      (node (ref "C30") (pin "2") (pinfunction "2_2") (pintype "passive"))
      (node (ref "R31") (pin "2") (pinfunction "2_2") (pintype "passive"))
      (node (ref "U3") (pin "2") (pinfunction "VC4_2") (pintype "input"))
    )
    (net (code "45") (name "Net-(U3-VC5)") (class "Default")
      (node (ref "C25") (pin "1") (pinfunction "1_1") (pintype "passive"))
      (node (ref "C28") (pin "2") (pinfunction "2_2") (pintype "passive"))
      (node (ref "R30") (pin "2") (pinfunction "2_2") (pintype "passive"))
      (node (ref "U3") (pin "1") (pinfunction "VC5_1") (pintype "input"))
    )
    (net (code "46") (name "Net-(U3-VC6)") (class "Default")
      (node (ref "C25") (pin "2") (pinfunction "2_2") (pintype "passive"))
      (node (ref "R25") (pin "2") (pinfunction "2_2") (pintype "passive"))
      (node (ref "U3") (pin "32") (pinfunction "VC6_32") (pintype "input"))
    )
    (net (code "47") (name "Net-(U3-VCC)") (class "Default")
      (node (ref "C21") (pin "2") (pinfunction "2_2") (pintype "passive"))
      (node (ref "C23") (pin "2") (pinfunction "2_2") (pintype "passive"))
      (node (ref "R22") (pin "1") (pinfunction "1_1") (pintype "passive"))
      (node (ref "U3") (pin "24") (pinfunction "VCC_24") (pintype "power_in"))
    )
    (net (code "48") (name "VBAT") (class "Default")
      (node (ref "C19") (pin "1") (pinfunction "1_1") (pintype "passive"))
      (node (ref "D7") (pin "2") (pintype "passive"))
      (node (ref "Q3") (pin "2") (pinfunction "Source_2") (pintype "passive"))
      (node (ref "Q5") (pin "2") (pinfunction "Source_2") (pintype "passive"))
      (node (ref "R16") (pin "1") (pinfunction "1_1") (pintype "passive"))
      (node (ref "R19") (pin "2") (pinfunction "2_2") (pintype "passive"))
      (node (ref "R25") (pin "1") (pinfunction "1_1") (pintype "passive"))
    )
  )
)
